# avr-nrf.net
KiCad netlist of a schematic drawn in EAGLE
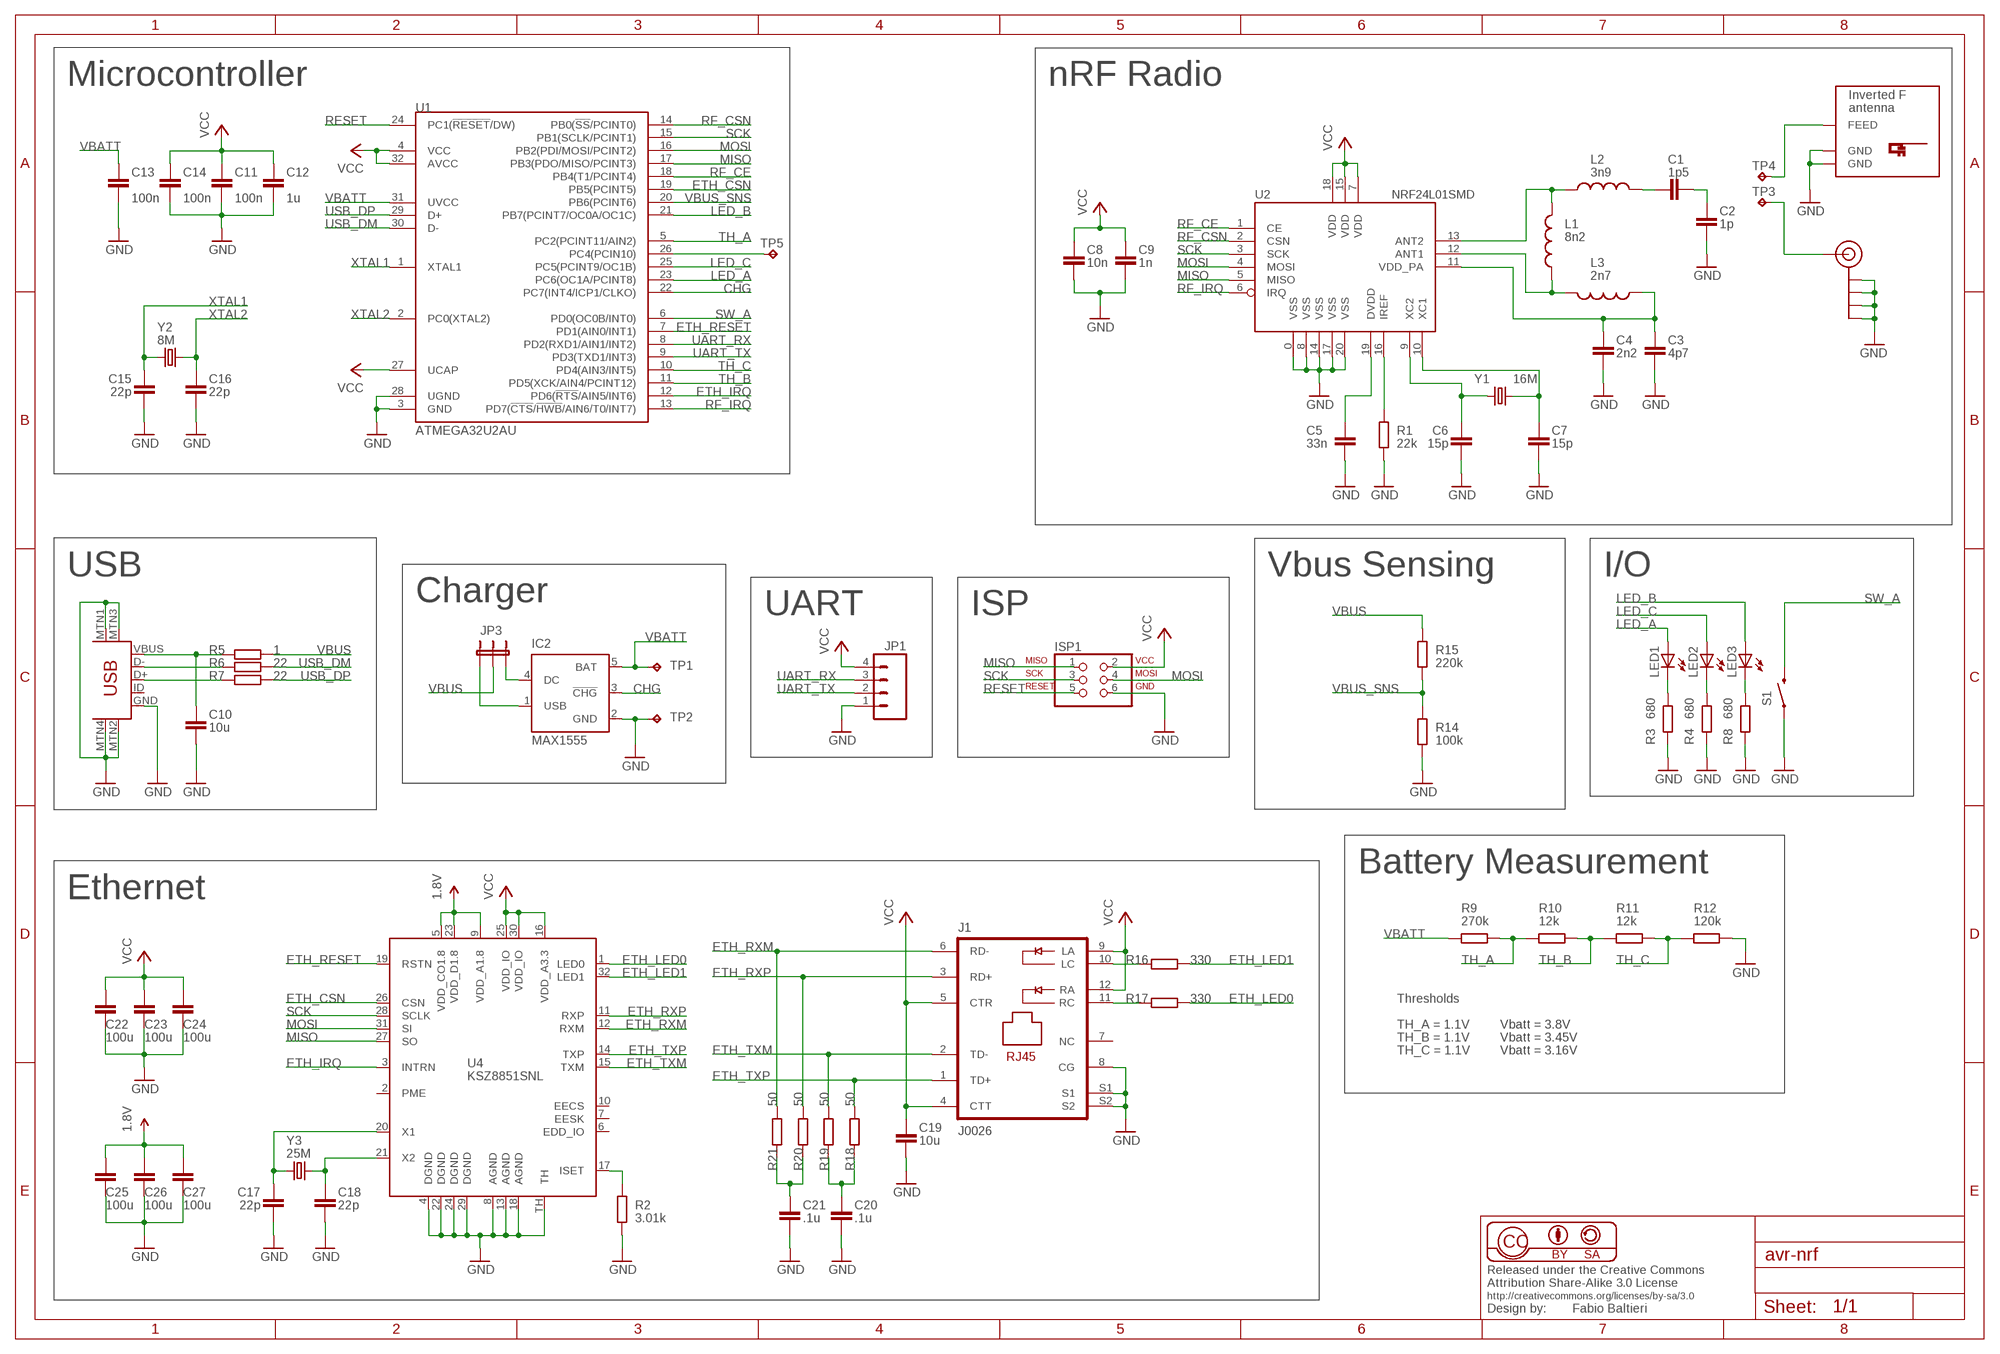
[diagram p0: schematic, sheet 1]

(export (version "E")
  (design (tool "Eeschema 10.0.6"))
  (components
    (comp (ref "C1")
      (value "1p5")
      (footprint "eagle-import:C0805")
      (libsource (lib "eagle-import") (part "C-EUC0805"))
    )
    (comp (ref "C2")
      (value "1p")
      (footprint "eagle-import:C0805")
      (libsource (lib "eagle-import") (part "C-EUC0805"))
    )
    (comp (ref "C3")
      (value "4p7")
      (footprint "eagle-import:C0805")
      (libsource (lib "eagle-import") (part "C-EUC0805"))
    )
    (comp (ref "C4")
      (value "2n2")
      (footprint "eagle-import:C0805")
      (libsource (lib "eagle-import") (part "C-EUC0805"))
    )
    (comp (ref "C5")
      (value "33n")
      (footprint "eagle-import:C0805")
      (libsource (lib "eagle-import") (part "C-EUC0805"))
    )
    (comp (ref "C6")
      (value "15p")
      (footprint "eagle-import:C0805")
      (libsource (lib "eagle-import") (part "C-EUC0805"))
    )
    (comp (ref "C7")
      (value "15p")
      (footprint "eagle-import:C0805")
      (libsource (lib "eagle-import") (part "C-EUC0805"))
    )
    (comp (ref "C8")
      (value "10n")
      (footprint "eagle-import:C0805")
      (libsource (lib "eagle-import") (part "C-EUC0805"))
    )
    (comp (ref "C9")
      (value "1n")
      (footprint "eagle-import:C0805")
      (libsource (lib "eagle-import") (part "C-EUC0805"))
    )
    (comp (ref "C10")
      (value "10u")
      (footprint "eagle-import:C0805")
      (libsource (lib "eagle-import") (part "C-EUC0805"))
    )
    (comp (ref "C11")
      (value "100n")
      (footprint "eagle-import:C0805")
      (libsource (lib "eagle-import") (part "C-EUC0805"))
    )
    (comp (ref "C12")
      (value "1u")
      (footprint "eagle-import:C0805")
      (libsource (lib "eagle-import") (part "C-EUC0805"))
    )
    (comp (ref "C13")
      (value "100n")
      (footprint "eagle-import:C0805")
      (libsource (lib "eagle-import") (part "C-EUC0805"))
    )
    (comp (ref "C14")
      (value "100n")
      (footprint "eagle-import:C0805")
      (libsource (lib "eagle-import") (part "C-EUC0805"))
    )
    (comp (ref "C15")
      (value "22p")
      (footprint "eagle-import:C0805")
      (libsource (lib "eagle-import") (part "C-EUC0805"))
    )
    (comp (ref "C16")
      (value "22p")
      (footprint "eagle-import:C0805")
      (libsource (lib "eagle-import") (part "C-EUC0805"))
    )
    (comp (ref "C17")
      (value "22p")
      (footprint "eagle-import:C0805")
      (libsource (lib "eagle-import") (part "C-EUC0805"))
    )
    (comp (ref "C18")
      (value "22p")
      (footprint "eagle-import:C0805")
      (libsource (lib "eagle-import") (part "C-EUC0805"))
    )
    (comp (ref "C19")
      (value "10u")
      (footprint "eagle-import:C0805")
      (libsource (lib "eagle-import") (part "C-EUC0805"))
    )
    (comp (ref "C20")
      (value ".1u")
      (footprint "eagle-import:C0805")
      (libsource (lib "eagle-import") (part "C-EUC0805"))
    )
    (comp (ref "C21")
      (value ".1u")
      (footprint "eagle-import:C0805")
      (libsource (lib "eagle-import") (part "C-EUC0805"))
    )
    (comp (ref "C22")
      (value "100u")
      (footprint "eagle-import:C0805")
      (libsource (lib "eagle-import") (part "C-EUC0805"))
    )
    (comp (ref "C23")
      (value "100u")
      (footprint "eagle-import:C0805")
      (libsource (lib "eagle-import") (part "C-EUC0805"))
    )
    (comp (ref "C24")
      (value "100u")
      (footprint "eagle-import:C0805")
      (libsource (lib "eagle-import") (part "C-EUC0805"))
    )
    (comp (ref "C25")
      (value "100u")
      (footprint "eagle-import:C0805")
      (libsource (lib "eagle-import") (part "C-EUC0805"))
    )
    (comp (ref "C26")
      (value "100u")
      (footprint "eagle-import:C0805")
      (libsource (lib "eagle-import") (part "C-EUC0805"))
    )
    (comp (ref "C27")
      (value "100u")
      (footprint "eagle-import:C0805")
      (libsource (lib "eagle-import") (part "C-EUC0805"))
    )
    (comp (ref "IC2")
      (value "MAX1555")
      (footprint "eagle-import:SOT23-5L")
      (libsource (lib "eagle-import") (part "MAX1555"))
    )
    (comp (ref "ISP1")
      (value "ISP-AVR910PTH")
      (footprint "eagle-import:2X03")
      (libsource (lib "eagle-import") (part "ISP-AVR910PTH"))
    )
    (comp (ref "J$1")
      (value "SMA_EDGE")
      (footprint "eagle-import:SMA-EDGE")
      (libsource (lib "eagle-import") (part "SMA_EDGE"))
    )
    (comp (ref "J1")
      (value "J0026")
      (footprint "eagle-import:PJ-J0")
      (libsource (lib "eagle-import") (part "J0026"))
    )
    (comp (ref "JP1")
      (value "M04PTH")
      (footprint "eagle-import:1X04")
      (libsource (lib "eagle-import") (part "M04PTH"))
    )
    (comp (ref "JP3")
      (value "JUMPER-3SMD")
      (footprint "eagle-import:SJ_3")
      (libsource (lib "eagle-import") (part "JUMPER-3SMD"))
    )
    (comp (ref "L1")
      (value "8n2")
      (footprint "eagle-import:0603")
      (libsource (lib "eagle-import") (part "INDUCTOR0603"))
    )
    (comp (ref "L2")
      (value "3n9")
      (footprint "eagle-import:0603")
      (libsource (lib "eagle-import") (part "INDUCTOR0603"))
    )
    (comp (ref "L3")
      (value "2n7")
      (footprint "eagle-import:0603")
      (libsource (lib "eagle-import") (part "INDUCTOR0603"))
    )
    (comp (ref "LED1")
      (value "LEDCHIPLED_0805")
      (footprint "eagle-import:CHIPLED_0805")
      (libsource (lib "eagle-import") (part "LEDCHIPLED_0805"))
    )
    (comp (ref "LED2")
      (value "LEDCHIPLED_0805")
      (footprint "eagle-import:CHIPLED_0805")
      (libsource (lib "eagle-import") (part "LEDCHIPLED_0805"))
    )
    (comp (ref "LED3")
      (value "LEDCHIPLED_0805")
      (footprint "eagle-import:CHIPLED_0805")
      (libsource (lib "eagle-import") (part "LEDCHIPLED_0805"))
    )
    (comp (ref "R1")
      (value "22k")
      (footprint "eagle-import:R0603")
      (libsource (lib "eagle-import") (part "R-EU_R0603"))
    )
    (comp (ref "R2")
      (value "3.01k")
      (footprint "eagle-import:R0603")
      (libsource (lib "eagle-import") (part "R-EU_R0603"))
    )
    (comp (ref "R3")
      (value "680")
      (footprint "eagle-import:R0603")
      (libsource (lib "eagle-import") (part "R-EU_R0603"))
    )
    (comp (ref "R4")
      (value "680")
      (footprint "eagle-import:R0603")
      (libsource (lib "eagle-import") (part "R-EU_R0603"))
    )
    (comp (ref "R5")
      (value "1")
      (footprint "eagle-import:R0603")
      (libsource (lib "eagle-import") (part "R-EU_R0603"))
    )
    (comp (ref "R6")
      (value "22")
      (footprint "eagle-import:R0603")
      (libsource (lib "eagle-import") (part "R-EU_R0603"))
    )
    (comp (ref "R7")
      (value "22")
      (footprint "eagle-import:R0603")
      (libsource (lib "eagle-import") (part "R-EU_R0603"))
    )
    (comp (ref "R8")
      (value "680")
      (footprint "eagle-import:R0603")
      (libsource (lib "eagle-import") (part "R-EU_R0603"))
    )
    (comp (ref "R9")
      (value "270k")
      (footprint "eagle-import:R0603")
      (libsource (lib "eagle-import") (part "R-EU_R0603"))
    )
    (comp (ref "R10")
      (value "12k")
      (footprint "eagle-import:R0603")
      (libsource (lib "eagle-import") (part "R-EU_R0603"))
    )
    (comp (ref "R11")
      (value "12k")
      (footprint "eagle-import:R0603")
      (libsource (lib "eagle-import") (part "R-EU_R0603"))
    )
    (comp (ref "R12")
      (value "120k")
      (footprint "eagle-import:R0603")
      (libsource (lib "eagle-import") (part "R-EU_R0603"))
    )
    (comp (ref "R14")
      (value "100k")
      (footprint "eagle-import:R0603")
      (libsource (lib "eagle-import") (part "R-EU_R0603"))
    )
    (comp (ref "R15")
      (value "220k")
      (footprint "eagle-import:R0603")
      (libsource (lib "eagle-import") (part "R-EU_R0603"))
    )
    (comp (ref "R16")
      (value "330")
      (footprint "eagle-import:R0603")
      (libsource (lib "eagle-import") (part "R-EU_R0603"))
    )
    (comp (ref "R17")
      (value "330")
      (footprint "eagle-import:R0603")
      (libsource (lib "eagle-import") (part "R-EU_R0603"))
    )
    (comp (ref "R18")
      (value "50")
      (footprint "eagle-import:R0603")
      (libsource (lib "eagle-import") (part "R-EU_R0603"))
    )
    (comp (ref "R19")
      (value "50")
      (footprint "eagle-import:R0603")
      (libsource (lib "eagle-import") (part "R-EU_R0603"))
    )
    (comp (ref "R20")
      (value "50")
      (footprint "eagle-import:R0603")
      (libsource (lib "eagle-import") (part "R-EU_R0603"))
    )
    (comp (ref "R21")
      (value "50")
      (footprint "eagle-import:R0603")
      (libsource (lib "eagle-import") (part "R-EU_R0603"))
    )
    (comp (ref "S1")
      (value "SWITCH-MOMENTARY-2SMD")
      (footprint "eagle-import:TACTILE_SWITCH_SMD")
      (libsource (lib "eagle-import") (part "SWITCH-MOMENTARY-2SMD"))
    )
    (comp (ref "TP1")
      (value "TPTP12R")
      (footprint "eagle-import:TP12R")
      (libsource (lib "eagle-import") (part "TPTP12R"))
    )
    (comp (ref "TP2")
      (value "TPTP12R")
      (footprint "eagle-import:TP12R")
      (libsource (lib "eagle-import") (part "TPTP12R"))
    )
    (comp (ref "TP3")
      (value "TPTP08SQ")
      (footprint "eagle-import:TP08SQ")
      (libsource (lib "eagle-import") (part "TPTP08SQ"))
    )
    (comp (ref "TP4")
      (value "TPTP08SQ")
      (footprint "eagle-import:TP08SQ")
      (libsource (lib "eagle-import") (part "TPTP08SQ"))
    )
    (comp (ref "TP5")
      (value "TPTP06R")
      (footprint "eagle-import:TP06R")
      (libsource (lib "eagle-import") (part "TPTP06R"))
    )
    (comp (ref "U$1")
      (value "INVERTED_F_ANTENNA+5")
      (footprint "eagle-import:DN007+5")
      (libsource (lib "eagle-import") (part "INVERTED_F_ANTENNA+5"))
    )
    (comp (ref "U1")
      (value "ATMEGA32U2AU")
      (footprint "eagle-import:TQFP32-08")
      (libsource (lib "eagle-import") (part "ATMEGA32U2AU"))
    )
    (comp (ref "U2")
      (value "NRF24L01SMD")
      (footprint "eagle-import:QFN20")
      (libsource (lib "eagle-import") (part "NRF24L01SMD"))
    )
    (comp (ref "U3")
      (value "USB-MINIB-5PIN")
      (footprint "eagle-import:USB-MINIB")
      (libsource (lib "eagle-import") (part "USB-MINIB-5PIN"))
    )
    (comp (ref "U4")
      (value "KSZ8851SNL")
      (footprint "eagle-import:MLF32-TH")
      (libsource (lib "eagle-import") (part "KSZ8851SNL"))
    )
    (comp (ref "Y1")
      (value "16M")
      (footprint "eagle-import:CRYSTAL-SMD-5X3")
      (libsource (lib "eagle-import") (part "CRYSTAL5X3"))
    )
    (comp (ref "Y2")
      (value "8M")
      (footprint "eagle-import:CRYSTAL-SMD-5X3")
      (libsource (lib "eagle-import") (part "CRYSTAL5X3"))
    )
    (comp (ref "Y3")
      (value "25M")
      (footprint "eagle-import:CRYSTAL-SMD-5X3")
      (libsource (lib "eagle-import") (part "CRYSTAL5X3"))
    )
  )
  (nets
    (net (code "1") (name "/CHG") (class "Default")
      (node (ref "IC2") (pin "3") (pinfunction "~{CHG}_3") (pintype "output"))
      (node (ref "U1") (pin "22") (pinfunction "PC7(INT4/ICP1/CLKO)_22") (pintype "bidirectional"))
    )
    (net (code "2") (name "/ETH_CSN") (class "Default")
      (node (ref "U1") (pin "19") (pinfunction "PB5(PCINT5)_19") (pintype "bidirectional"))
      (node (ref "U4") (pin "26") (pinfunction "CSN_26") (pintype "bidirectional"))
    )
    (net (code "3") (name "/ETH_IRQ") (class "Default")
      (node (ref "U1") (pin "12") (pinfunction "PD6(~{RTS}/AIN5/INT6)_12") (pintype "bidirectional"))
      (node (ref "U4") (pin "3") (pinfunction "INTRN_3") (pintype "bidirectional"))
    )
    (net (code "4") (name "/ETH_LED0") (class "Default")
      (node (ref "R17") (pin "2") (pinfunction "2_2") (pintype "passive"))
      (node (ref "U4") (pin "1") (pinfunction "LED0_1") (pintype "bidirectional"))
    )
    (net (code "5") (name "/ETH_LED1") (class "Default")
      (node (ref "R16") (pin "2") (pinfunction "2_2") (pintype "passive"))
      (node (ref "U4") (pin "32") (pinfunction "LED1_32") (pintype "bidirectional"))
    )
    (net (code "6") (name "/ETH_RESET") (class "Default")
      (node (ref "U1") (pin "7") (pinfunction "PD1(AIN0/INT1)_7") (pintype "bidirectional"))
      (node (ref "U4") (pin "19") (pinfunction "RSTN_19") (pintype "bidirectional"))
    )
    (net (code "7") (name "/ETH_RXM") (class "Default")
      (node (ref "J1") (pin "6") (pinfunction "RD-_6") (pintype "bidirectional"))
      (node (ref "R21") (pin "2") (pinfunction "2_2") (pintype "passive"))
      (node (ref "U4") (pin "12") (pinfunction "RXM_12") (pintype "bidirectional"))
    )
    (net (code "8") (name "/ETH_RXP") (class "Default")
      (node (ref "J1") (pin "3") (pinfunction "RD+_3") (pintype "bidirectional"))
      (node (ref "R20") (pin "2") (pinfunction "2_2") (pintype "passive"))
      (node (ref "U4") (pin "11") (pinfunction "RXP_11") (pintype "bidirectional"))
    )
    (net (code "9") (name "/ETH_TXM") (class "Default")
      (node (ref "J1") (pin "2") (pinfunction "TD-_2") (pintype "bidirectional"))
      (node (ref "R19") (pin "2") (pinfunction "2_2") (pintype "passive"))
      (node (ref "U4") (pin "15") (pinfunction "TXM_15") (pintype "bidirectional"))
    )
    (net (code "10") (name "/ETH_TXP") (class "Default")
      (node (ref "J1") (pin "1") (pinfunction "TD+_1") (pintype "bidirectional"))
      (node (ref "R18") (pin "2") (pinfunction "2_2") (pintype "passive"))
      (node (ref "U4") (pin "14") (pinfunction "TXP_14") (pintype "bidirectional"))
    )
    (net (code "11") (name "/LED_A") (class "Default")
      (node (ref "LED1") (pin "A") (pinfunction "A_A") (pintype "passive"))
      (node (ref "U1") (pin "23") (pinfunction "PC6(OC1A/PCINT8)_23") (pintype "bidirectional"))
    )
    (net (code "12") (name "/LED_B") (class "Default")
      (node (ref "LED3") (pin "A") (pinfunction "A_A") (pintype "passive"))
      (node (ref "U1") (pin "21") (pinfunction "PB7(PCINT7/OC0A/OC1C)_21") (pintype "bidirectional"))
    )
    (net (code "13") (name "/LED_C") (class "Default")
      (node (ref "LED2") (pin "A") (pinfunction "A_A") (pintype "passive"))
      (node (ref "U1") (pin "25") (pinfunction "PC5(PCINT9/OC1B)_25") (pintype "bidirectional"))
    )
    (net (code "14") (name "/MISO") (class "Default")
      (node (ref "ISP1") (pin "1") (pinfunction "1_1") (pintype "passive"))
      (node (ref "U1") (pin "17") (pinfunction "PB3(PDO/MISO/PCINT3)_17") (pintype "bidirectional"))
      (node (ref "U2") (pin "5") (pinfunction "MISO_5") (pintype "output"))
      (node (ref "U4") (pin "27") (pinfunction "SO_27") (pintype "bidirectional"))
    )
    (net (code "15") (name "/MOSI") (class "Default")
      (node (ref "ISP1") (pin "4") (pinfunction "4_4") (pintype "passive"))
      (node (ref "U1") (pin "16") (pinfunction "PB2(PDI/MOSI/PCINT2)_16") (pintype "bidirectional"))
      (node (ref "U2") (pin "4") (pinfunction "MOSI_4") (pintype "input"))
      (node (ref "U4") (pin "31") (pinfunction "SI_31") (pintype "bidirectional"))
    )
    (net (code "16") (name "/RESET") (class "Default")
      (node (ref "ISP1") (pin "5") (pinfunction "5_5") (pintype "passive"))
      (node (ref "U1") (pin "24") (pinfunction "PC1(~{RESET}/DW)_24") (pintype "bidirectional"))
    )
    (net (code "17") (name "/RF_CE") (class "Default")
      (node (ref "U1") (pin "18") (pinfunction "PB4(T1/PCINT4)_18") (pintype "bidirectional"))
      (node (ref "U2") (pin "1") (pinfunction "CE_1") (pintype "input"))
    )
    (net (code "18") (name "/RF_CSN") (class "Default")
      (node (ref "U1") (pin "14") (pinfunction "PB0(~{SS}/PCINT0)_14") (pintype "bidirectional"))
      (node (ref "U2") (pin "2") (pinfunction "CSN_2") (pintype "input"))
    )
    (net (code "19") (name "/RF_IRQ") (class "Default")
      (node (ref "U1") (pin "13") (pinfunction "PD7(~{CTS}/~{HWB}/AIN6/T0/INT7)_13") (pintype "bidirectional"))
      (node (ref "U2") (pin "6") (pinfunction "IRQ_6") (pintype "output"))
    )
    (net (code "20") (name "/SCK") (class "Default")
      (node (ref "ISP1") (pin "3") (pinfunction "3_3") (pintype "passive"))
      (node (ref "U1") (pin "15") (pinfunction "PB1(SCLK/PCINT1)_15") (pintype "bidirectional"))
      (node (ref "U2") (pin "3") (pinfunction "SCK_3") (pintype "input"))
      (node (ref "U4") (pin "28") (pinfunction "SCLK_28") (pintype "bidirectional"))
    )
    (net (code "21") (name "/SW_A") (class "Default")
      (node (ref "S1") (pin "3") (pinfunction "2_3") (pintype "passive"))
      (node (ref "U1") (pin "6") (pinfunction "PD0(OC0B/INT0)_6") (pintype "bidirectional"))
    )
    (net (code "22") (name "/TH_A") (class "Default")
      (node (ref "R10") (pin "2") (pinfunction "2_2") (pintype "passive"))
      (node (ref "R9") (pin "1") (pinfunction "1_1") (pintype "passive"))
      (node (ref "U1") (pin "5") (pinfunction "PC2(PCINT11/AIN2)_5") (pintype "bidirectional"))
    )
    (net (code "23") (name "/TH_B") (class "Default")
      (node (ref "R10") (pin "1") (pinfunction "1_1") (pintype "passive"))
      (node (ref "R11") (pin "2") (pinfunction "2_2") (pintype "passive"))
      (node (ref "U1") (pin "11") (pinfunction "PD5(XCK/AIN4/PCINT12)_11") (pintype "bidirectional"))
    )
    (net (code "24") (name "/TH_C") (class "Default")
      (node (ref "R11") (pin "1") (pinfunction "1_1") (pintype "passive"))
      (node (ref "R12") (pin "2") (pinfunction "2_2") (pintype "passive"))
      (node (ref "U1") (pin "10") (pinfunction "PD4(AIN3/INT5)_10") (pintype "bidirectional"))
    )
    (net (code "25") (name "/UART_RX") (class "Default")
      (node (ref "JP1") (pin "3") (pinfunction "3_3") (pintype "passive"))
      (node (ref "U1") (pin "8") (pinfunction "PD2(RXD1/AIN1/INT2)_8") (pintype "bidirectional"))
    )
    (net (code "26") (name "/UART_TX") (class "Default")
      (node (ref "JP1") (pin "2") (pinfunction "2_2") (pintype "passive"))
      (node (ref "U1") (pin "9") (pinfunction "PD3(TXD1/INT3)_9") (pintype "bidirectional"))
    )
    (net (code "27") (name "/USB_DM") (class "Default")
      (node (ref "R6") (pin "2") (pinfunction "2_2") (pintype "passive"))
      (node (ref "U1") (pin "30") (pinfunction "D-_30") (pintype "bidirectional"))
    )
    (net (code "28") (name "/USB_DP") (class "Default")
      (node (ref "R7") (pin "2") (pinfunction "2_2") (pintype "passive"))
      (node (ref "U1") (pin "29") (pinfunction "D+_29") (pintype "bidirectional"))
    )
    (net (code "29") (name "/VBATT") (class "Default")
      (node (ref "C13") (pin "1") (pinfunction "1_1") (pintype "passive"))
      (node (ref "IC2") (pin "5") (pinfunction "BAT_5") (pintype "passive"))
      (node (ref "R9") (pin "2") (pinfunction "2_2") (pintype "passive"))
      (node (ref "TP1") (pin "TP") (pinfunction "TP_TP") (pintype "input"))
      (node (ref "U1") (pin "31") (pinfunction "UVCC_31") (pintype "bidirectional"))
    )
    (net (code "30") (name "/VBUS") (class "Default")
      (node (ref "JP3") (pin "2") (pinfunction "2_2") (pintype "passive"))
      (node (ref "R15") (pin "1") (pinfunction "1_1") (pintype "passive"))
      (node (ref "R5") (pin "2") (pinfunction "2_2") (pintype "passive"))
    )
    (net (code "31") (name "/VBUS_SNS") (class "Default")
      (node (ref "R14") (pin "1") (pinfunction "1_1") (pintype "passive"))
      (node (ref "R15") (pin "2") (pinfunction "2_2") (pintype "passive"))
      (node (ref "U1") (pin "20") (pinfunction "PB6(PCINT6)_20") (pintype "bidirectional"))
    )
    (net (code "32") (name "/XTAL1") (class "Default")
      (node (ref "C15") (pin "1") (pinfunction "1_1") (pintype "passive"))
      (node (ref "U1") (pin "1") (pinfunction "XTAL1_1") (pintype "bidirectional"))
      (node (ref "Y2") (pin "1") (pinfunction "1_1") (pintype "passive"))
    )
    (net (code "33") (name "/XTAL2") (class "Default")
      (node (ref "C16") (pin "1") (pinfunction "1_1") (pintype "passive"))
      (node (ref "U1") (pin "2") (pinfunction "PC0(XTAL2)_2") (pintype "bidirectional"))
      (node (ref "Y2") (pin "3") (pinfunction "2_3") (pintype "passive"))
    )
    (net (code "34") (name "1.8V") (class "Default")
      (node (ref "C25") (pin "1") (pinfunction "1_1") (pintype "passive"))
      (node (ref "C26") (pin "1") (pinfunction "1_1") (pintype "passive"))
      (node (ref "C27") (pin "1") (pinfunction "1_1") (pintype "passive"))
      (node (ref "U4") (pin "23") (pinfunction "VDD_D1.8_23") (pintype "bidirectional"))
      (node (ref "U4") (pin "5") (pinfunction "VDD_CO1.8_5") (pintype "bidirectional"))
      (node (ref "U4") (pin "9") (pinfunction "VDD_A1.8_9") (pintype "bidirectional"))
    )
    (net (code "35") (name "GND") (class "Default")
      (node (ref "C10") (pin "2") (pinfunction "2_2") (pintype "passive"))
      (node (ref "C11") (pin "2") (pinfunction "2_2") (pintype "passive"))
      (node (ref "C12") (pin "2") (pinfunction "2_2") (pintype "passive"))
      (node (ref "C13") (pin "2") (pinfunction "2_2") (pintype "passive"))
      (node (ref "C14") (pin "2") (pinfunction "2_2") (pintype "passive"))
      (node (ref "C15") (pin "2") (pinfunction "2_2") (pintype "passive"))
      (node (ref "C16") (pin "2") (pinfunction "2_2") (pintype "passive"))
      (node (ref "C17") (pin "2") (pinfunction "2_2") (pintype "passive"))
      (node (ref "C18") (pin "2") (pinfunction "2_2") (pintype "passive"))
      (node (ref "C19") (pin "2") (pinfunction "2_2") (pintype "passive"))
      (node (ref "C2") (pin "2") (pinfunction "2_2") (pintype "passive"))
      (node (ref "C20") (pin "2") (pinfunction "2_2") (pintype "passive"))
      (node (ref "C21") (pin "2") (pinfunction "2_2") (pintype "passive"))
      (node (ref "C22") (pin "2") (pinfunction "2_2") (pintype "passive"))
      (node (ref "C23") (pin "2") (pinfunction "2_2") (pintype "passive"))
      (node (ref "C24") (pin "2") (pinfunction "2_2") (pintype "passive"))
      (node (ref "C25") (pin "2") (pinfunction "2_2") (pintype "passive"))
      (node (ref "C26") (pin "2") (pinfunction "2_2") (pintype "passive"))
      (node (ref "C27") (pin "2") (pinfunction "2_2") (pintype "passive"))
      (node (ref "C3") (pin "2") (pinfunction "2_2") (pintype "passive"))
      (node (ref "C4") (pin "2") (pinfunction "2_2") (pintype "passive"))
      (node (ref "C5") (pin "2") (pinfunction "2_2") (pintype "passive"))
      (node (ref "C6") (pin "2") (pinfunction "2_2") (pintype "passive"))
      (node (ref "C7") (pin "2") (pinfunction "2_2") (pintype "passive"))
      (node (ref "C8") (pin "2") (pinfunction "2_2") (pintype "passive"))
      (node (ref "C9") (pin "2") (pinfunction "2_2") (pintype "passive"))
      (node (ref "IC2") (pin "2") (pinfunction "GND_2") (pintype "power_in"))
      (node (ref "ISP1") (pin "6") (pinfunction "6_6") (pintype "passive"))
      (node (ref "J$1") (pin "GND@0") (pinfunction "GND_GND@0") (pintype "bidirectional"))
      (node (ref "J$1") (pin "GND@1") (pinfunction "GND_GND@1") (pintype "bidirectional"))
      (node (ref "J$1") (pin "GND@2") (pinfunction "GND_GND@2") (pintype "bidirectional"))
      (node (ref "J$1") (pin "GND@3") (pinfunction "GND_GND@3") (pintype "bidirectional"))
      (node (ref "J1") (pin "8") (pinfunction "CG_8") (pintype "passive"))
      (node (ref "J1") (pin "S1") (pinfunction "S1_S1") (pintype "passive"))
      (node (ref "J1") (pin "S2") (pinfunction "S2_S2") (pintype "passive"))
      (node (ref "JP1") (pin "1") (pinfunction "1_1") (pintype "passive"))
      (node (ref "R1") (pin "2") (pinfunction "2_2") (pintype "passive"))
      (node (ref "R12") (pin "1") (pinfunction "1_1") (pintype "passive"))
      (node (ref "R14") (pin "2") (pinfunction "2_2") (pintype "passive"))
      (node (ref "R2") (pin "2") (pinfunction "2_2") (pintype "passive"))
      (node (ref "R3") (pin "2") (pinfunction "2_2") (pintype "passive"))
      (node (ref "R4") (pin "2") (pinfunction "2_2") (pintype "passive"))
      (node (ref "R8") (pin "2") (pinfunction "2_2") (pintype "passive"))
      (node (ref "S1") (pin "1") (pinfunction "1_1") (pintype "passive"))
      (node (ref "TP2") (pin "TP") (pinfunction "TP_TP") (pintype "input"))
      (node (ref "U$1") (pin "GND") (pinfunction "GND_GND") (pintype "bidirectional"))
      (node (ref "U$1") (pin "GND@1") (pinfunction "GND_GND@1") (pintype "bidirectional"))
      (node (ref "U1") (pin "28") (pinfunction "UGND_28") (pintype "bidirectional"))
      (node (ref "U1") (pin "3") (pinfunction "GND_3") (pintype "bidirectional"))
      (node (ref "U2") (pin "0") (pinfunction "VSS_0") (pintype "power_in"))
      (node (ref "U2") (pin "14") (pinfunction "VSS_14") (pintype "power_in"))
      (node (ref "U2") (pin "17") (pinfunction "VSS_17") (pintype "power_in"))
      (node (ref "U2") (pin "20") (pinfunction "VSS_20") (pintype "power_in"))
      (node (ref "U2") (pin "8") (pinfunction "VSS_8") (pintype "power_in"))
      (node (ref "U3") (pin "GND") (pinfunction "GND_GND") (pintype "bidirectional"))
      (node (ref "U3") (pin "MTN1") (pinfunction "MTN2_MTN1") (pintype "bidirectional"))
      (node (ref "U3") (pin "MTN2") (pinfunction "MTN3_MTN2") (pintype "bidirectional"))
      (node (ref "U3") (pin "MTN3") (pinfunction "MTN1_MTN3") (pintype "bidirectional"))
      (node (ref "U3") (pin "MTN4") (pinfunction "MTN4_MTN4") (pintype "bidirectional"))
      (node (ref "U4") (pin "13") (pinfunction "AGND_13") (pintype "bidirectional"))
      (node (ref "U4") (pin "18") (pinfunction "AGND_18") (pintype "bidirectional"))
      (node (ref "U4") (pin "22") (pinfunction "DGND_22") (pintype "bidirectional"))
      (node (ref "U4") (pin "24") (pinfunction "DGND_24") (pintype "bidirectional"))
      (node (ref "U4") (pin "29") (pinfunction "DGND_29") (pintype "bidirectional"))
      (node (ref "U4") (pin "4") (pinfunction "DGND_4") (pintype "bidirectional"))
      (node (ref "U4") (pin "8") (pinfunction "AGND_8") (pintype "bidirectional"))
      (node (ref "U4") (pin "TH") (pinfunction "TH_TH") (pintype "bidirectional"))
    )
    (net (code "36") (name "Net-(C1-Pad1)") (class "Default")
      (node (ref "C1") (pin "1") (pinfunction "1_1") (pintype "passive"))
      (node (ref "L2") (pin "2") (pinfunction "2_2") (pintype "passive"))
    )
    (net (code "37") (name "Net-(C1-Pad2)") (class "Default")
      (node (ref "C1") (pin "2") (pinfunction "2_2") (pintype "passive"))
      (node (ref "C2") (pin "1") (pinfunction "1_1") (pintype "passive"))
    )
    (net (code "38") (name "Net-(C10-Pad1)") (class "Default")
      (node (ref "C10") (pin "1") (pinfunction "1_1") (pintype "passive"))
      (node (ref "R5") (pin "1") (pinfunction "1_1") (pintype "passive"))
      (node (ref "U3") (pin "VBUS") (pinfunction "VBUS_VBUS") (pintype "bidirectional"))
    )
    (net (code "39") (name "Net-(C20-Pad1)") (class "Default")
      (node (ref "C20") (pin "1") (pinfunction "1_1") (pintype "passive"))
      (node (ref "R18") (pin "1") (pinfunction "1_1") (pintype "passive"))
      (node (ref "R19") (pin "1") (pinfunction "1_1") (pintype "passive"))
    )
    (net (code "40") (name "Net-(C21-Pad1)") (class "Default")
      (node (ref "C21") (pin "1") (pinfunction "1_1") (pintype "passive"))
      (node (ref "R20") (pin "1") (pinfunction "1_1") (pintype "passive"))
      (node (ref "R21") (pin "1") (pinfunction "1_1") (pintype "passive"))
    )
    (net (code "41") (name "Net-(IC2-DC)") (class "Default")
      (node (ref "IC2") (pin "4") (pinfunction "DC_4") (pintype "input"))
      (node (ref "JP3") (pin "3") (pinfunction "3_3") (pintype "passive"))
    )
    (net (code "42") (name "Net-(IC2-USB)") (class "Default")
      (node (ref "IC2") (pin "1") (pinfunction "USB_1") (pintype "input"))
      (node (ref "JP3") (pin "1") (pinfunction "1_1") (pintype "passive"))
    )
    (net (code "43") (name "Net-(J$1-SIGNAL)") (class "Default")
      (node (ref "J$1") (pin "SIG") (pinfunction "SIGNAL_SIG") (pintype "bidirectional"))
      (node (ref "TP3") (pin "TP") (pinfunction "TP_TP") (pintype "input"))
    )
    (net (code "44") (name "Net-(J1-LC)") (class "Default")
      (node (ref "J1") (pin "10") (pinfunction "LC_10") (pintype "passive"))
      (node (ref "R16") (pin "1") (pinfunction "1_1") (pintype "passive"))
    )
    (net (code "45") (name "Net-(J1-RC)") (class "Default")
      (node (ref "J1") (pin "11") (pinfunction "RC_11") (pintype "passive"))
      (node (ref "R17") (pin "1") (pinfunction "1_1") (pintype "passive"))
    )
    (net (code "46") (name "Net-(LED1-PadC)") (class "Default")
      (node (ref "LED1") (pin "C") (pinfunction "C_C") (pintype "passive"))
      (node (ref "R3") (pin "1") (pinfunction "1_1") (pintype "passive"))
    )
    (net (code "47") (name "Net-(LED2-PadC)") (class "Default")
      (node (ref "LED2") (pin "C") (pinfunction "C_C") (pintype "passive"))
      (node (ref "R4") (pin "1") (pinfunction "1_1") (pintype "passive"))
    )
    (net (code "48") (name "Net-(LED3-PadC)") (class "Default")
      (node (ref "LED3") (pin "C") (pinfunction "C_C") (pintype "passive"))
      (node (ref "R8") (pin "1") (pinfunction "1_1") (pintype "passive"))
    )
    (net (code "49") (name "Net-(R6-Pad1)") (class "Default")
      (node (ref "R6") (pin "1") (pinfunction "1_1") (pintype "passive"))
      (node (ref "U3") (pin "D-") (pinfunction "D-_D-") (pintype "bidirectional"))
    )
    (net (code "50") (name "Net-(R7-Pad1)") (class "Default")
      (node (ref "R7") (pin "1") (pinfunction "1_1") (pintype "passive"))
      (node (ref "U3") (pin "D+") (pinfunction "D+_D+") (pintype "bidirectional"))
    )
    (net (code "51") (name "Net-(TP4-PadTP)") (class "Default")
      (node (ref "TP4") (pin "TP") (pinfunction "TP_TP") (pintype "input"))
      (node (ref "U$1") (pin "FEED") (pinfunction "FEED_FEED") (pintype "bidirectional"))
    )
    (net (code "52") (name "Net-(U1-PC4(PCIN10))") (class "Default")
      (node (ref "TP5") (pin "TP") (pinfunction "TP_TP") (pintype "input"))
      (node (ref "U1") (pin "26") (pinfunction "PC4(PCIN10)_26") (pintype "bidirectional"))
    )
    (net (code "53") (name "Net-(U2-ANT1)") (class "Default")
      (node (ref "L1") (pin "2") (pinfunction "2_2") (pintype "passive"))
      (node (ref "L3") (pin "2") (pinfunction "2_2") (pintype "passive"))
      (node (ref "U2") (pin "12") (pinfunction "ANT1_12") (pintype "output"))
    )
    (net (code "54") (name "Net-(U2-ANT2)") (class "Default")
      (node (ref "L1") (pin "1") (pinfunction "1_1") (pintype "passive"))
      (node (ref "L2") (pin "1") (pinfunction "1_1") (pintype "passive"))
      (node (ref "U2") (pin "13") (pinfunction "ANT2_13") (pintype "output"))
    )
    (net (code "55") (name "Net-(U2-DVDD)") (class "Default")
      (node (ref "C5") (pin "1") (pinfunction "1_1") (pintype "passive"))
      (node (ref "U2") (pin "19") (pinfunction "DVDD_19") (pintype "power_in"))
    )
    (net (code "56") (name "Net-(U2-IREF)") (class "Default")
      (node (ref "R1") (pin "1") (pinfunction "1_1") (pintype "passive"))
      (node (ref "U2") (pin "16") (pinfunction "IREF_16") (pintype "input"))
    )
    (net (code "57") (name "Net-(U2-VDD_PA)") (class "Default")
      (node (ref "C3") (pin "1") (pinfunction "1_1") (pintype "passive"))
      (node (ref "C4") (pin "1") (pinfunction "1_1") (pintype "passive"))
      (node (ref "L3") (pin "1") (pinfunction "1_1") (pintype "passive"))
      (node (ref "U2") (pin "11") (pinfunction "VDD_PA_11") (pintype "power_in"))
    )
    (net (code "58") (name "Net-(U2-XC1)") (class "Default")
      (node (ref "C7") (pin "1") (pinfunction "1_1") (pintype "passive"))
      (node (ref "U2") (pin "10") (pinfunction "XC1_10") (pintype "input"))
      (node (ref "Y1") (pin "3") (pinfunction "2_3") (pintype "passive"))
    )
    (net (code "59") (name "Net-(U2-XC2)") (class "Default")
      (node (ref "C6") (pin "1") (pinfunction "1_1") (pintype "passive"))
      (node (ref "U2") (pin "9") (pinfunction "XC2_9") (pintype "input"))
      (node (ref "Y1") (pin "1") (pinfunction "1_1") (pintype "passive"))
    )
    (net (code "60") (name "Net-(U4-ISET)") (class "Default")
      (node (ref "R2") (pin "1") (pinfunction "1_1") (pintype "passive"))
      (node (ref "U4") (pin "17") (pinfunction "ISET_17") (pintype "bidirectional"))
    )
    (net (code "61") (name "Net-(U4-X1)") (class "Default")
      (node (ref "C17") (pin "1") (pinfunction "1_1") (pintype "passive"))
      (node (ref "U4") (pin "20") (pinfunction "X1_20") (pintype "bidirectional"))
      (node (ref "Y3") (pin "1") (pinfunction "1_1") (pintype "passive"))
    )
    (net (code "62") (name "Net-(U4-X2)") (class "Default")
      (node (ref "C18") (pin "1") (pinfunction "1_1") (pintype "passive"))
      (node (ref "U4") (pin "21") (pinfunction "X2_21") (pintype "bidirectional"))
      (node (ref "Y3") (pin "3") (pinfunction "2_3") (pintype "passive"))
    )
    (net (code "63") (name "VCC") (class "Default")
      (node (ref "C11") (pin "1") (pinfunction "1_1") (pintype "passive"))
      (node (ref "C12") (pin "1") (pinfunction "1_1") (pintype "passive"))
      (node (ref "C14") (pin "1") (pinfunction "1_1") (pintype "passive"))
      (node (ref "C19") (pin "1") (pinfunction "1_1") (pintype "passive"))
      (node (ref "C22") (pin "1") (pinfunction "1_1") (pintype "passive"))
      (node (ref "C23") (pin "1") (pinfunction "1_1") (pintype "passive"))
      (node (ref "C24") (pin "1") (pinfunction "1_1") (pintype "passive"))
      (node (ref "C8") (pin "1") (pinfunction "1_1") (pintype "passive"))
      (node (ref "C9") (pin "1") (pinfunction "1_1") (pintype "passive"))
      (node (ref "ISP1") (pin "2") (pinfunction "2_2") (pintype "passive"))
      (node (ref "J1") (pin "12") (pinfunction "RA_12") (pintype "passive"))
      (node (ref "J1") (pin "4") (pinfunction "CTT_4") (pintype "bidirectional"))
      (node (ref "J1") (pin "5") (pinfunction "CTR_5") (pintype "bidirectional"))
      (node (ref "J1") (pin "9") (pinfunction "LA_9") (pintype "passive"))
      (node (ref "JP1") (pin "4") (pinfunction "4_4") (pintype "passive"))
      (node (ref "U1") (pin "27") (pinfunction "UCAP_27") (pintype "bidirectional"))
      (node (ref "U1") (pin "32") (pinfunction "AVCC_32") (pintype "bidirectional"))
      (node (ref "U1") (pin "4") (pinfunction "VCC_4") (pintype "bidirectional"))
      (node (ref "U2") (pin "15") (pinfunction "VDD_15") (pintype "power_in"))
      (node (ref "U2") (pin "18") (pinfunction "VDD_18") (pintype "power_in"))
      (node (ref "U2") (pin "7") (pinfunction "VDD_7") (pintype "power_in"))
      (node (ref "U4") (pin "16") (pinfunction "VDD_A3.3_16") (pintype "bidirectional"))
      (node (ref "U4") (pin "25") (pinfunction "VDD_IO_25") (pintype "bidirectional"))
      (node (ref "U4") (pin "30") (pinfunction "VDD_IO_30") (pintype "bidirectional"))
    )
    (net (code "64") (name "unconnected-(J1-NC-Pad7)") (class "Default")
      (node (ref "J1") (pin "7") (pinfunction "NC_7") (pintype "passive"))
    )
    (net (code "65") (name "unconnected-(U3-PadID)") (class "Default")
      (node (ref "U3") (pin "ID") (pinfunction "ID_ID") (pintype "bidirectional"))
    )
    (net (code "66") (name "unconnected-(U4-EDD_IO-Pad6)") (class "Default")
      (node (ref "U4") (pin "6") (pinfunction "EDD_IO_6") (pintype "bidirectional"))
    )
    (net (code "67") (name "unconnected-(U4-EECS-Pad10)") (class "Default")
      (node (ref "U4") (pin "10") (pinfunction "EECS_10") (pintype "bidirectional"))
    )
    (net (code "68") (name "unconnected-(U4-EESK-Pad7)") (class "Default")
      (node (ref "U4") (pin "7") (pinfunction "EESK_7") (pintype "bidirectional"))
    )
    (net (code "69") (name "unconnected-(U4-PME-Pad2)") (class "Default")
      (node (ref "U4") (pin "2") (pinfunction "PME_2") (pintype "bidirectional"))
    )
  )
)
